# filter-7.net
KiCad netlist of a schematic drawn in Altium Designer
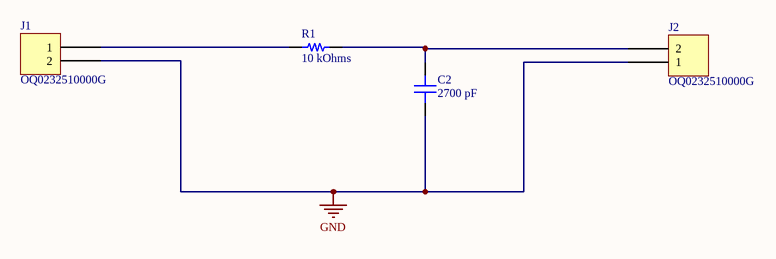
[diagram p0: filter-7.SchDoc]

(export (version "E")
  (design (tool "Eeschema 10.0.6"))
  (components
    (comp (ref "C2")
      (value "2700 pF")
      (footprint "CAP 0603_1608")
      (description "CAP CER 2700PF 25V NP0 0603")
      (fields (field (name "PART NUMBER") "C0603C272F3GAC7867") (field (name "MANUFACTURER") "KEMET"))
      (libsource (lib "Celestial Altium Library - altium_library") (part "Capacitor"))
    )
    (comp (ref "J1")
      (value "OQ0232510000G")
      (footprint "FCI 06-381-2PIN")
      (description "TERM BLOCK HDR 2POS 90DEG 3.81MM")
      (fields (field (name "MANUFACTURER") "Amphenol Anytek"))
      (libsource (lib "") (part "2 Pin_1"))
    )
    (comp (ref "J2")
      (value "OQ0232510000G")
      (footprint "FCI 06-381-2PIN")
      (description "TERM BLOCK HDR 2POS 90DEG 3.81MM")
      (fields (field (name "MANUFACTURER") "Amphenol Anytek"))
      (libsource (lib "Celestial Altium Library - altium_library") (part "2 Pin"))
    )
    (comp (ref "R1")
      (value "10 kOhms")
      (footprint "RES 0603_1608")
      (description "RES 10K OHM 0.1% 1/16W 0603")
      (fields
        (field (name "PART NUMBER") "RNCS0603BKE10K0")
        (field (name "MANUFACTURER") "Stackpole Electronics Inc")
      )
      (libsource (lib "Celestial Altium Library - altium_library") (part "Resistor"))
    )
  )
  (nets
    (net (code "1") (name "GND") (class "Default")
      (node (ref "C2") (pin "1") (pinfunction "1_1") (pintype "passive"))
      (node (ref "J1") (pin "2") (pinfunction "2_2") (pintype "passive"))
      (node (ref "J2") (pin "1") (pinfunction "1_1") (pintype "passive"))
    )
    (net (code "2") (name "Net-(C2-Pad2)") (class "Default")
      (node (ref "C2") (pin "2") (pinfunction "2_2") (pintype "passive"))
      (node (ref "J2") (pin "2") (pinfunction "2_2") (pintype "passive"))
      (node (ref "R1") (pin "2") (pinfunction "2_2") (pintype "passive"))
    )
    (net (code "3") (name "Net-(J1-Pad1)") (class "Default")
      (node (ref "J1") (pin "1") (pinfunction "1_1") (pintype "passive"))
      (node (ref "R1") (pin "1") (pinfunction "1_1") (pintype "passive"))
    )
  )
)
